# msp430g2553in20-test-board.net
KiCad netlist of a schematic drawn in EAGLE
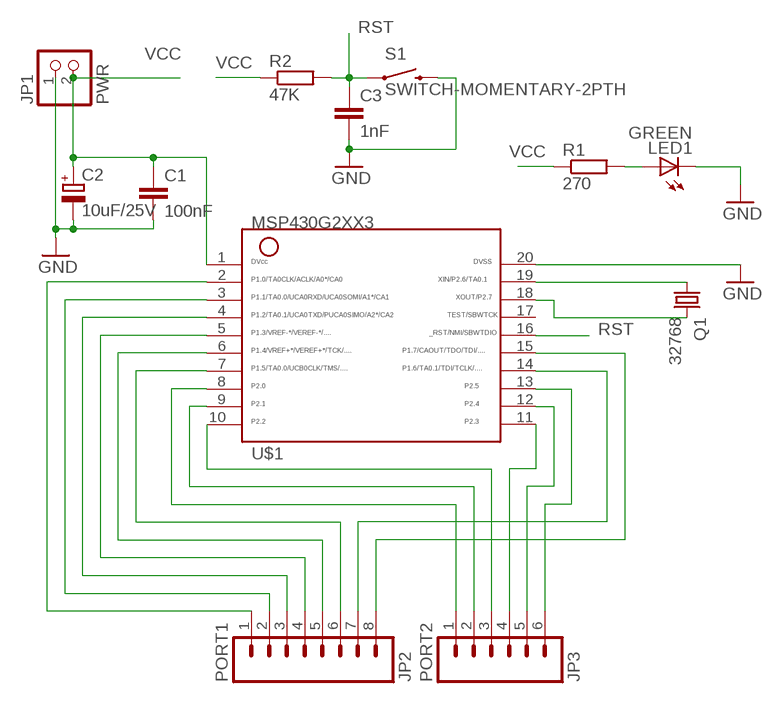
[diagram p0: schematic, sheet 1]

(export (version "E")
  (design (tool "Eeschema 10.0.6"))
  (components
    (comp (ref "C1")
      (value "100nF")
      (footprint "eagle-import:C025-025X050")
      (libsource (lib "eagle-import") (part "C-EU025-025X050"))
    )
    (comp (ref "C2")
      (value "10uF/25V")
      (footprint "eagle-import:E2-5")
      (libsource (lib "eagle-import") (part "CPOL-EUE2-5"))
    )
    (comp (ref "C3")
      (value "1nF")
      (footprint "eagle-import:C025-025X050")
      (libsource (lib "eagle-import") (part "C-EU025-025X050"))
    )
    (comp (ref "JP1")
      (value "PWR")
      (footprint "eagle-import:1X02")
      (libsource (lib "eagle-import") (part "PINHD-1X2"))
    )
    (comp (ref "JP2")
      (value "PORT1")
      (footprint "eagle-import:1X08")
      (libsource (lib "eagle-import") (part "M081X08"))
    )
    (comp (ref "JP3")
      (value "PORT2")
      (footprint "eagle-import:1X06")
      (libsource (lib "eagle-import") (part "M06SIP"))
    )
    (comp (ref "LED1")
      (value "GREEN")
      (footprint "eagle-import:LED3MM")
      (libsource (lib "eagle-import") (part "LED3MM"))
    )
    (comp (ref "Q1")
      (value "32768")
      (footprint "eagle-import:TC38H")
      (libsource (lib "eagle-import") (part "CRYSTALTC38H"))
    )
    (comp (ref "R1")
      (value "270")
      (footprint "eagle-import:0204_5")
      (libsource (lib "eagle-import") (part "R-EU_0204/5"))
    )
    (comp (ref "R2")
      (value "47K")
      (footprint "eagle-import:0204_5")
      (libsource (lib "eagle-import") (part "R-EU_0204/5"))
    )
    (comp (ref "S1")
      (value "SWITCH-MOMENTARY-2PTH")
      (footprint "eagle-import:TACTILE-PTH")
      (libsource (lib "eagle-import") (part "SWITCH-MOMENTARY-2PTH"))
    )
    (comp (ref "U$1")
      (value "G2XX3---N20")
      (footprint "eagle-import:N20")
      (libsource (lib "eagle-import") (part "G2XX3---N20"))
    )
  )
  (nets
    (net (code "1") (name "/RST") (class "Default")
      (node (ref "C3") (pin "1") (pinfunction "1_1") (pintype "passive"))
      (node (ref "R2") (pin "2") (pinfunction "2_2") (pintype "passive"))
      (node (ref "S1") (pin "1") (pinfunction "1_1") (pintype "passive"))
      (node (ref "U$1") (pin "16") (pinfunction "16_16") (pintype "bidirectional"))
    )
    (net (code "2") (name "/VCC") (class "Default")
      (node (ref "C1") (pin "1") (pinfunction "1_1") (pintype "passive"))
      (node (ref "C2") (pin "+") (pinfunction "+_+") (pintype "passive"))
      (node (ref "JP1") (pin "2") (pinfunction "2_2") (pintype "passive"))
      (node (ref "R1") (pin "1") (pinfunction "1_1") (pintype "passive"))
      (node (ref "R2") (pin "1") (pinfunction "1_1") (pintype "passive"))
      (node (ref "U$1") (pin "1") (pinfunction "1_1") (pintype "bidirectional"))
    )
    (net (code "3") (name "GND") (class "Default")
      (node (ref "C1") (pin "2") (pinfunction "2_2") (pintype "passive"))
      (node (ref "C2") (pin "-") (pinfunction "-_-") (pintype "passive"))
      (node (ref "C3") (pin "2") (pinfunction "2_2") (pintype "passive"))
      (node (ref "JP1") (pin "1") (pinfunction "1_1") (pintype "passive"))
      (node (ref "LED1") (pin "K") (pinfunction "C_K") (pintype "passive"))
      (node (ref "S1") (pin "3") (pinfunction "2_3") (pintype "passive"))
      (node (ref "U$1") (pin "20") (pinfunction "20_20") (pintype "bidirectional"))
    )
    (net (code "4") (name "Net-(JP2-Pad1)") (class "Default")
      (node (ref "JP2") (pin "1") (pinfunction "1_1") (pintype "passive"))
      (node (ref "U$1") (pin "2") (pinfunction "2_2") (pintype "bidirectional"))
    )
    (net (code "5") (name "Net-(JP2-Pad2)") (class "Default")
      (node (ref "JP2") (pin "2") (pinfunction "2_2") (pintype "passive"))
      (node (ref "U$1") (pin "3") (pinfunction "3_3") (pintype "bidirectional"))
    )
    (net (code "6") (name "Net-(JP2-Pad3)") (class "Default")
      (node (ref "JP2") (pin "3") (pinfunction "3_3") (pintype "passive"))
      (node (ref "U$1") (pin "4") (pinfunction "4_4") (pintype "bidirectional"))
    )
    (net (code "7") (name "Net-(JP2-Pad4)") (class "Default")
      (node (ref "JP2") (pin "4") (pinfunction "4_4") (pintype "passive"))
      (node (ref "U$1") (pin "5") (pinfunction "5_5") (pintype "bidirectional"))
    )
    (net (code "8") (name "Net-(JP2-Pad5)") (class "Default")
      (node (ref "JP2") (pin "5") (pinfunction "5_5") (pintype "passive"))
      (node (ref "U$1") (pin "6") (pinfunction "6_6") (pintype "bidirectional"))
    )
    (net (code "9") (name "Net-(JP2-Pad6)") (class "Default")
      (node (ref "JP2") (pin "6") (pinfunction "6_6") (pintype "passive"))
      (node (ref "U$1") (pin "7") (pinfunction "7_7") (pintype "bidirectional"))
    )
    (net (code "10") (name "Net-(JP2-Pad7)") (class "Default")
      (node (ref "JP2") (pin "7") (pinfunction "7_7") (pintype "passive"))
      (node (ref "U$1") (pin "14") (pinfunction "14_14") (pintype "bidirectional"))
    )
    (net (code "11") (name "Net-(JP2-Pad8)") (class "Default")
      (node (ref "JP2") (pin "8") (pinfunction "8_8") (pintype "passive"))
      (node (ref "U$1") (pin "15") (pinfunction "15_15") (pintype "bidirectional"))
    )
    (net (code "12") (name "Net-(JP3-Pad1)") (class "Default")
      (node (ref "JP3") (pin "1") (pinfunction "1_1") (pintype "passive"))
      (node (ref "U$1") (pin "8") (pinfunction "8_8") (pintype "bidirectional"))
    )
    (net (code "13") (name "Net-(JP3-Pad2)") (class "Default")
      (node (ref "JP3") (pin "2") (pinfunction "2_2") (pintype "passive"))
      (node (ref "U$1") (pin "9") (pinfunction "9_9") (pintype "bidirectional"))
    )
    (net (code "14") (name "Net-(JP3-Pad3)") (class "Default")
      (node (ref "JP3") (pin "3") (pinfunction "3_3") (pintype "passive"))
      (node (ref "U$1") (pin "10") (pinfunction "10_10") (pintype "bidirectional"))
    )
    (net (code "15") (name "Net-(JP3-Pad4)") (class "Default")
      (node (ref "JP3") (pin "4") (pinfunction "4_4") (pintype "passive"))
      (node (ref "U$1") (pin "11") (pinfunction "11_11") (pintype "bidirectional"))
    )
    (net (code "16") (name "Net-(JP3-Pad5)") (class "Default")
      (node (ref "JP3") (pin "5") (pinfunction "5_5") (pintype "passive"))
      (node (ref "U$1") (pin "12") (pinfunction "12_12") (pintype "bidirectional"))
    )
    (net (code "17") (name "Net-(JP3-Pad6)") (class "Default")
      (node (ref "JP3") (pin "6") (pinfunction "6_6") (pintype "passive"))
      (node (ref "U$1") (pin "13") (pinfunction "13_13") (pintype "bidirectional"))
    )
    (net (code "18") (name "Net-(LED1-PadA)") (class "Default")
      (node (ref "LED1") (pin "A") (pinfunction "A_A") (pintype "passive"))
      (node (ref "R1") (pin "2") (pinfunction "2_2") (pintype "passive"))
    )
    (net (code "19") (name "Net-(Q1-Pad1)") (class "Default")
      (node (ref "Q1") (pin "1") (pinfunction "1_1") (pintype "passive"))
      (node (ref "U$1") (pin "19") (pinfunction "19_19") (pintype "bidirectional"))
    )
    (net (code "20") (name "Net-(Q1-Pad2)") (class "Default")
      (node (ref "Q1") (pin "2") (pinfunction "2_2") (pintype "passive"))
      (node (ref "U$1") (pin "18") (pinfunction "18_18") (pintype "bidirectional"))
    )
    (net (code "21") (name "unconnected-(U$1-Pad17)") (class "Default")
      (node (ref "U$1") (pin "17") (pinfunction "17_17") (pintype "bidirectional"))
    )
  )
)
